# PDC_Gain_Driver.net
KiCad netlist of a schematic drawn in Altium Designer
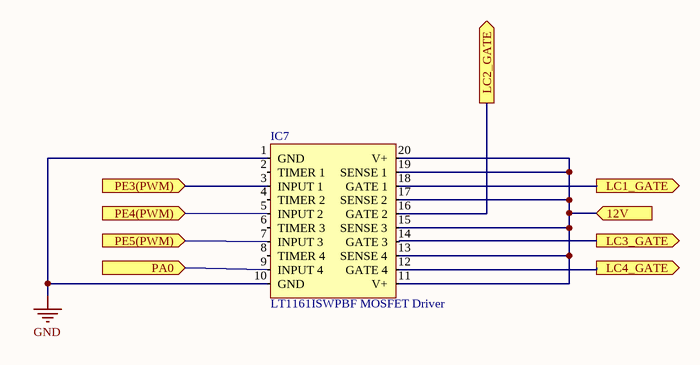
[diagram p0: PDC_Gain_Driver.SchDoc]

(export (version "E")
  (design (tool "Eeschema 10.0.6"))
  (components
    (comp (ref "IC7")
      (value "LT1161ISWPBF MOSFET Driver")
      (footprint "SO-20")
      (fields (field (name "CREATED_BY") "Eunice Bernardo"))
      (libsource (lib "Altium-Lib") (part "LT1161ISWPBF MOSFET Driver"))
    )
  )
  (nets
    (net (code "1") (name "/12V") (class "Default")
      (node (ref "IC7") (pin "11") (pinfunction "V+_11") (pintype "input"))
      (node (ref "IC7") (pin "13") (pinfunction "SENSE_4_13") (pintype "input"))
      (node (ref "IC7") (pin "15") (pinfunction "SENSE_3_15") (pintype "input"))
      (node (ref "IC7") (pin "17") (pinfunction "SENSE_2_17") (pintype "input"))
      (node (ref "IC7") (pin "19") (pinfunction "SENSE_1_19") (pintype "input"))
      (node (ref "IC7") (pin "20") (pinfunction "V+_20") (pintype "input"))
    )
    (net (code "2") (name "/LC1_GATE") (class "Default")
      (node (ref "IC7") (pin "18") (pinfunction "GATE_1_18") (pintype "input"))
    )
    (net (code "3") (name "/LC2_GATE") (class "Default")
      (node (ref "IC7") (pin "16") (pinfunction "GATE_2_16") (pintype "input"))
    )
    (net (code "4") (name "/LC3_GATE") (class "Default")
      (node (ref "IC7") (pin "14") (pinfunction "GATE_3_14") (pintype "input"))
    )
    (net (code "5") (name "/LC4_GATE") (class "Default")
      (node (ref "IC7") (pin "12") (pinfunction "GATE_4_12") (pintype "input"))
    )
    (net (code "6") (name "/PA0") (class "Default")
      (node (ref "IC7") (pin "9") (pinfunction "INPUT_4_9") (pintype "input"))
    )
    (net (code "7") (name "/PE3(PWM)") (class "Default")
      (node (ref "IC7") (pin "3") (pinfunction "INPUT_1_3") (pintype "input"))
    )
    (net (code "8") (name "/PE4(PWM)") (class "Default")
      (node (ref "IC7") (pin "5") (pinfunction "INPUT_2_5") (pintype "input"))
    )
    (net (code "9") (name "/PE5(PWM)") (class "Default")
      (node (ref "IC7") (pin "7") (pinfunction "INPUT_3_7") (pintype "input"))
    )
    (net (code "10") (name "GND") (class "Default")
      (node (ref "IC7") (pin "1") (pinfunction "GND_1") (pintype "input"))
      (node (ref "IC7") (pin "10") (pinfunction "GND_10") (pintype "input"))
    )
    (net (code "11") (name "unconnected-(IC7-TIMER_1-Pad2)") (class "Default")
      (node (ref "IC7") (pin "2") (pinfunction "TIMER_1_2") (pintype "input"))
    )
    (net (code "12") (name "unconnected-(IC7-TIMER_2-Pad4)") (class "Default")
      (node (ref "IC7") (pin "4") (pinfunction "TIMER_2_4") (pintype "input"))
    )
    (net (code "13") (name "unconnected-(IC7-TIMER_3-Pad6)") (class "Default")
      (node (ref "IC7") (pin "6") (pinfunction "TIMER_3_6") (pintype "input"))
    )
    (net (code "14") (name "unconnected-(IC7-TIMER_4-Pad8)") (class "Default")
      (node (ref "IC7") (pin "8") (pinfunction "TIMER_4_8") (pintype "input"))
    )
  )
)
